# MARS3.net
KiCad netlist of a schematic drawn in Altium Designer
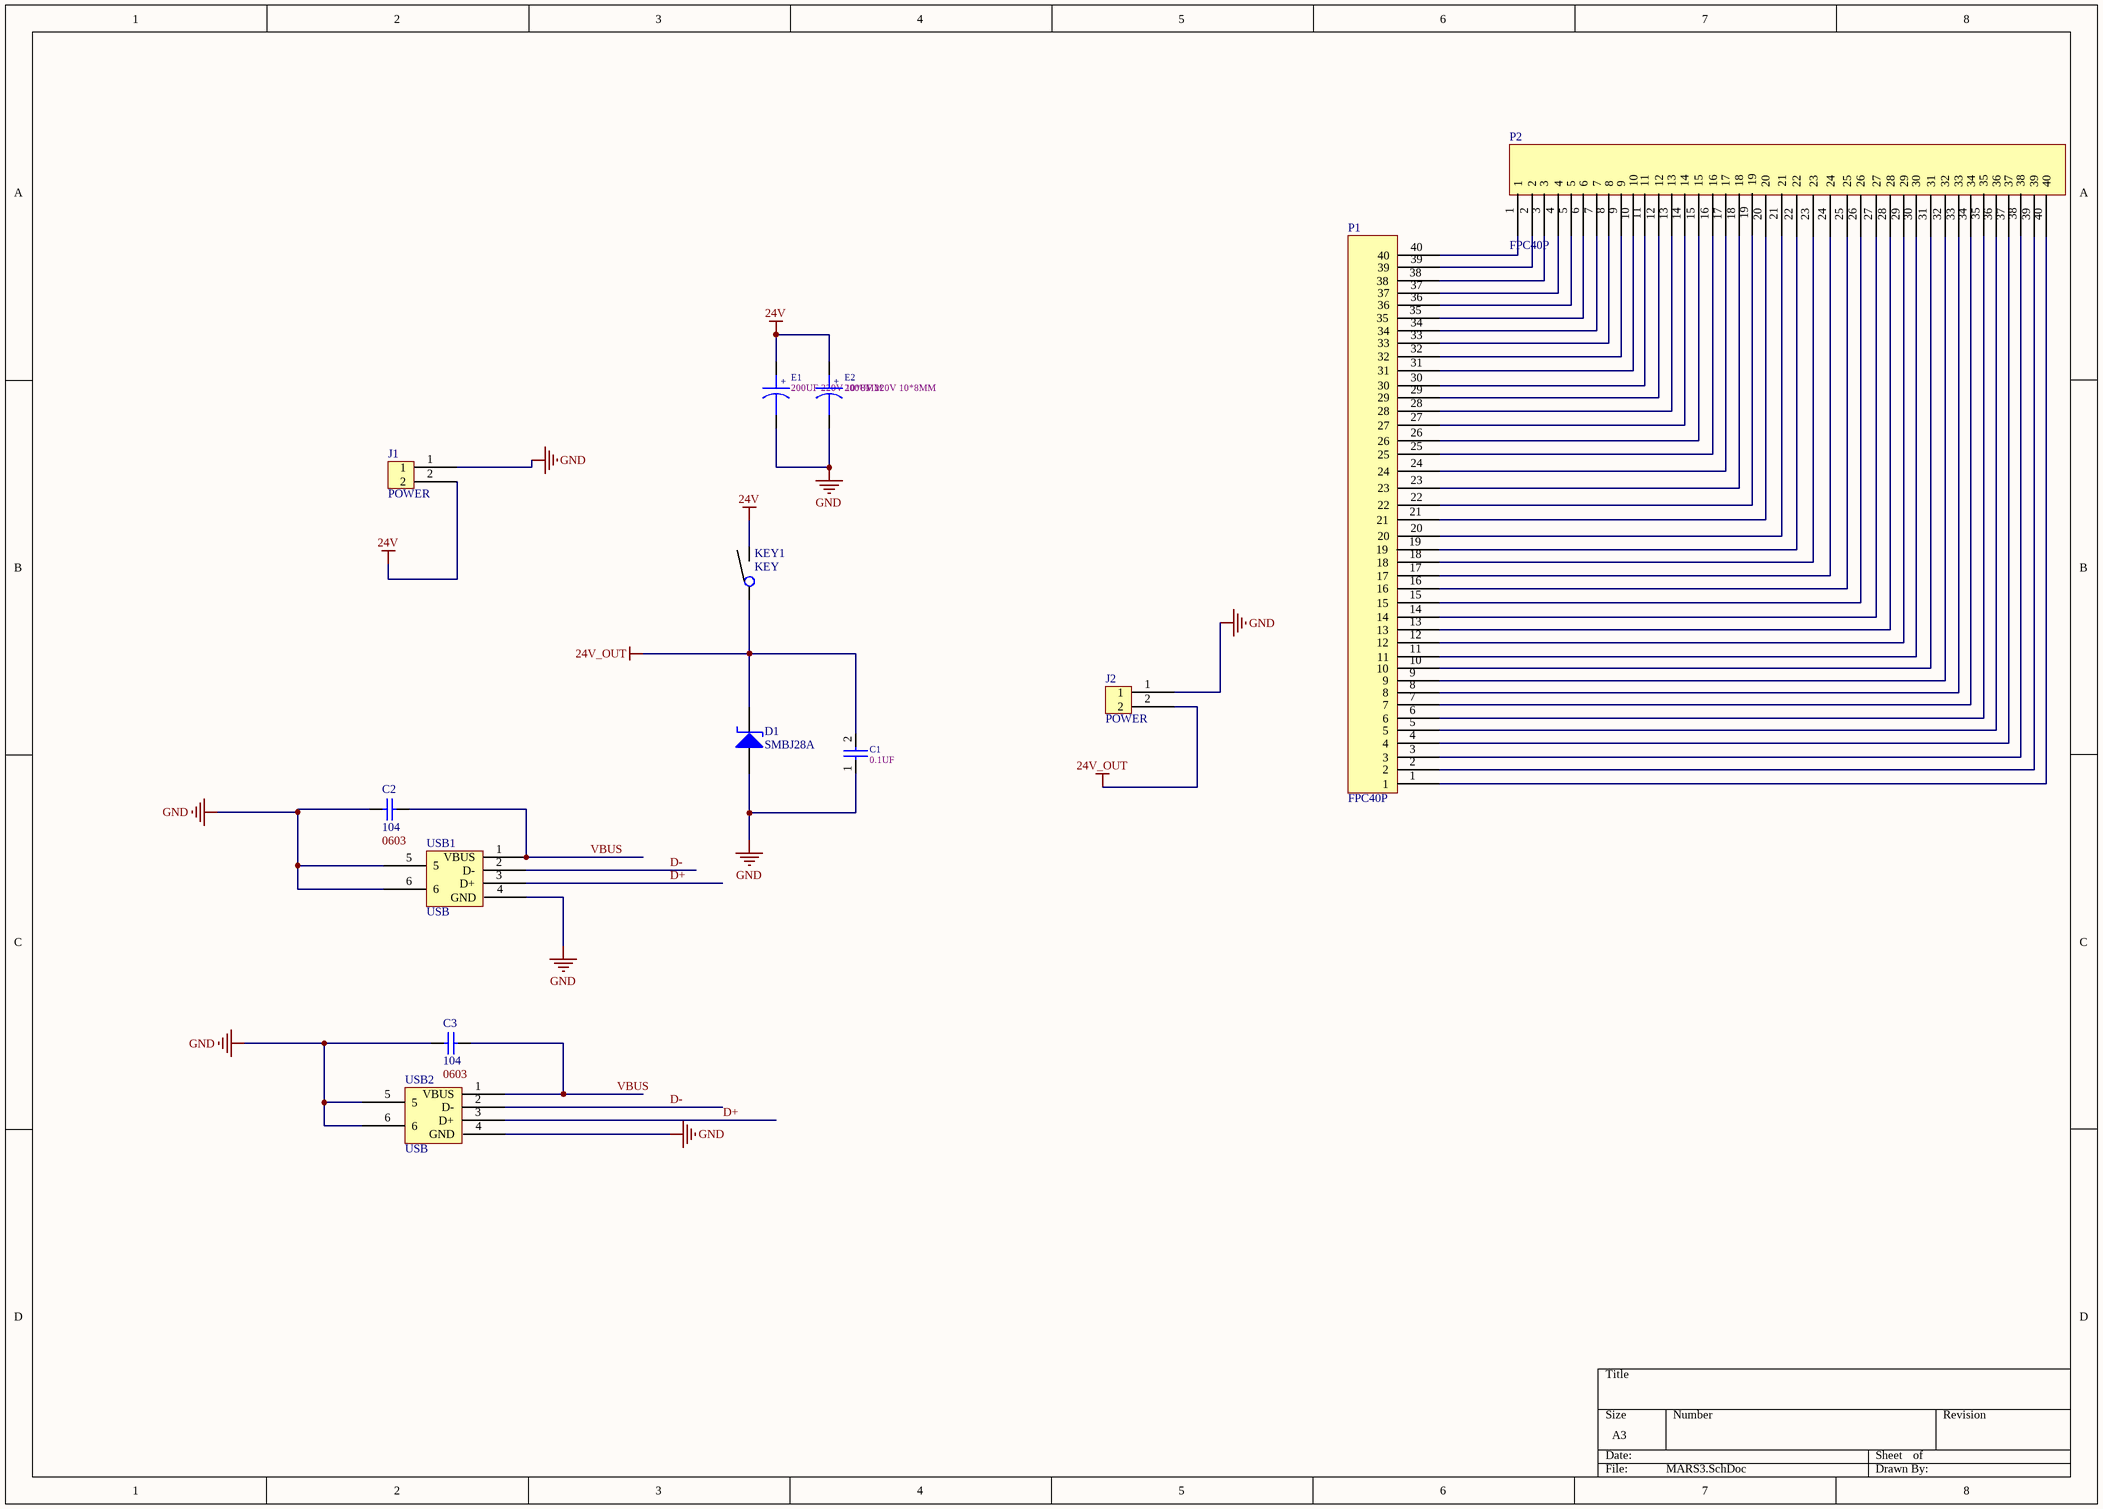
[diagram p0: MARS3.SchDoc]

(export (version "E")
  (design (tool "Eeschema 10.0.6"))
  (components
    (comp (ref "C1")
      (value "0.1UF")
      (footprint "C0603")
      (description "Capacitor")
      (libsource (lib "清洗固化") (part "CAP_10"))
    )
    (comp (ref "C2")
      (value "104")
      (footprint "0603")
      (description "Capacitor")
      (fields (field (name "PUBLISHER") "Altium Limited"))
      (libsource (lib "清洗机旋钮开关") (part "Cap_1"))
    )
    (comp (ref "C3")
      (value "104")
      (footprint "0603")
      (description "Capacitor")
      (fields (field (name "PUBLISHER") "Altium Limited"))
      (libsource (lib "清洗机旋钮开关") (part "Cap_1"))
    )
    (comp (ref "D1") (value "SMBJ28A") (footprint "DO214AA") (libsource (lib "清洗机旋钮开关") (part "TVS")))
    (comp (ref "E1")
      (value "200UF 220V 10*8MM")
      (footprint "CAPAE7766X80M")
      (description "Capacitor")
      (libsource (lib "清洗固化") (part "CAPACITOR POL"))
    )
    (comp (ref "E2")
      (value "200UF 220V 10*8MM")
      (footprint "CAPAE7766X80M")
      (description "Capacitor")
      (libsource (lib "清洗固化") (part "CAPACITOR POL"))
    )
    (comp (ref "J1")
      (value "POWER")
      (footprint "VH3.96_2P")
      (libsource (lib "VVH3.96_2P") (part "VH3.96_2P"))
    )
    (comp (ref "J2")
      (value "POWER")
      (footprint "VH3.96_2P")
      (libsource (lib "VVH3.96_2P") (part "VH3.96_2P"))
    )
    (comp (ref "KEY1") (value "KEY") (footprint "KEY") (libsource (lib "KEY") (part "KEY")))
    (comp (ref "P1") (value "FPC40P") (footprint "FPC0.5_40PIN") (libsource (lib "") (part "FPC40P_1")))
    (comp (ref "P2") (value "FPC40P") (footprint "FPC0.5_40PIN") (libsource (lib "FPC40P") (part "FPC40P")))
    (comp (ref "USB1") (value "USB") (footprint "USB_A_90_母座") (libsource (lib "USB_A母头") (part "USB_A母头")))
    (comp (ref "USB2") (value "USB") (footprint "USB10_SMT") (libsource (lib "USB_A母头") (part "USB_A母头")))
  )
  (nets
    (net (code "1") (name "/D+") (class "Default")
      (node (ref "USB1") (pin "3") (pinfunction "D+_3") (pintype "passive"))
      (node (ref "USB2") (pin "3") (pinfunction "D+_3") (pintype "passive"))
    )
    (net (code "2") (name "/D-") (class "Default")
      (node (ref "USB1") (pin "2") (pinfunction "D-_2") (pintype "passive"))
      (node (ref "USB2") (pin "2") (pinfunction "D-_2") (pintype "passive"))
    )
    (net (code "3") (name "/VBUS") (class "Default")
      (node (ref "C2") (pin "2") (pinfunction "2_2") (pintype "passive"))
      (node (ref "C3") (pin "2") (pinfunction "2_2") (pintype "passive"))
      (node (ref "USB1") (pin "1") (pinfunction "VBUS_1") (pintype "passive"))
      (node (ref "USB2") (pin "1") (pinfunction "VBUS_1") (pintype "passive"))
    )
    (net (code "4") (name "24V") (class "Default")
      (node (ref "E1") (pin "1") (pinfunction "1_1") (pintype "passive"))
      (node (ref "E2") (pin "1") (pinfunction "1_1") (pintype "passive"))
      (node (ref "J1") (pin "2") (pinfunction "2_2") (pintype "passive"))
      (node (ref "KEY1") (pin "2") (pinfunction "2_2") (pintype "passive"))
    )
    (net (code "5") (name "24V_OUT") (class "Default")
      (node (ref "C1") (pin "2") (pinfunction "2_2") (pintype "passive"))
      (node (ref "D1") (pin "2") (pinfunction "K_2") (pintype "passive"))
      (node (ref "J2") (pin "2") (pinfunction "2_2") (pintype "passive"))
      (node (ref "KEY1") (pin "1") (pinfunction "1_1") (pintype "passive"))
    )
    (net (code "6") (name "GND") (class "Default")
      (node (ref "C1") (pin "1") (pinfunction "1_1") (pintype "passive"))
      (node (ref "C2") (pin "1") (pinfunction "1_1") (pintype "passive"))
      (node (ref "C3") (pin "1") (pinfunction "1_1") (pintype "passive"))
      (node (ref "D1") (pin "1") (pinfunction "A_1") (pintype "passive"))
      (node (ref "E1") (pin "2") (pinfunction "2_2") (pintype "passive"))
      (node (ref "E2") (pin "2") (pinfunction "2_2") (pintype "passive"))
      (node (ref "J1") (pin "1") (pinfunction "1_1") (pintype "passive"))
      (node (ref "J2") (pin "1") (pinfunction "1_1") (pintype "passive"))
      (node (ref "USB1") (pin "4") (pinfunction "GND_4") (pintype "passive"))
      (node (ref "USB1") (pin "5") (pinfunction "5_5") (pintype "passive"))
      (node (ref "USB1") (pin "6") (pinfunction "6_6") (pintype "passive"))
      (node (ref "USB2") (pin "4") (pinfunction "GND_4") (pintype "passive"))
      (node (ref "USB2") (pin "5") (pinfunction "5_5") (pintype "passive"))
      (node (ref "USB2") (pin "6") (pinfunction "6_6") (pintype "passive"))
    )
    (net (code "7") (name "Net-(P1-Pad1)") (class "Default")
      (node (ref "P1") (pin "1") (pinfunction "1_1") (pintype "passive"))
      (node (ref "P2") (pin "40") (pinfunction "40_40") (pintype "passive"))
    )
    (net (code "8") (name "Net-(P1-Pad2)") (class "Default")
      (node (ref "P1") (pin "2") (pinfunction "2_2") (pintype "passive"))
      (node (ref "P2") (pin "39") (pinfunction "39_39") (pintype "passive"))
    )
    (net (code "9") (name "Net-(P1-Pad3)") (class "Default")
      (node (ref "P1") (pin "3") (pinfunction "3_3") (pintype "passive"))
      (node (ref "P2") (pin "38") (pinfunction "38_38") (pintype "passive"))
    )
    (net (code "10") (name "Net-(P1-Pad4)") (class "Default")
      (node (ref "P1") (pin "4") (pinfunction "4_4") (pintype "passive"))
      (node (ref "P2") (pin "37") (pinfunction "37_37") (pintype "passive"))
    )
    (net (code "11") (name "Net-(P1-Pad5)") (class "Default")
      (node (ref "P1") (pin "5") (pinfunction "5_5") (pintype "passive"))
      (node (ref "P2") (pin "36") (pinfunction "36_36") (pintype "passive"))
    )
    (net (code "12") (name "Net-(P1-Pad6)") (class "Default")
      (node (ref "P1") (pin "6") (pinfunction "6_6") (pintype "passive"))
      (node (ref "P2") (pin "35") (pinfunction "35_35") (pintype "passive"))
    )
    (net (code "13") (name "Net-(P1-Pad7)") (class "Default")
      (node (ref "P1") (pin "7") (pinfunction "7_7") (pintype "passive"))
      (node (ref "P2") (pin "34") (pinfunction "34_34") (pintype "passive"))
    )
    (net (code "14") (name "Net-(P1-Pad8)") (class "Default")
      (node (ref "P1") (pin "8") (pinfunction "8_8") (pintype "passive"))
      (node (ref "P2") (pin "33") (pinfunction "33_33") (pintype "passive"))
    )
    (net (code "15") (name "Net-(P1-Pad9)") (class "Default")
      (node (ref "P1") (pin "9") (pinfunction "9_9") (pintype "passive"))
      (node (ref "P2") (pin "32") (pinfunction "32_32") (pintype "passive"))
    )
    (net (code "16") (name "Net-(P1-Pad10)") (class "Default")
      (node (ref "P1") (pin "10") (pinfunction "10_10") (pintype "passive"))
      (node (ref "P2") (pin "31") (pinfunction "31_31") (pintype "passive"))
    )
    (net (code "17") (name "Net-(P1-Pad11)") (class "Default")
      (node (ref "P1") (pin "11") (pinfunction "11_11") (pintype "passive"))
      (node (ref "P2") (pin "30") (pinfunction "30_30") (pintype "passive"))
    )
    (net (code "18") (name "Net-(P1-Pad12)") (class "Default")
      (node (ref "P1") (pin "12") (pinfunction "12_12") (pintype "passive"))
      (node (ref "P2") (pin "29") (pinfunction "29_29") (pintype "passive"))
    )
    (net (code "19") (name "Net-(P1-Pad13)") (class "Default")
      (node (ref "P1") (pin "13") (pinfunction "13_13") (pintype "passive"))
      (node (ref "P2") (pin "28") (pinfunction "28_28") (pintype "passive"))
    )
    (net (code "20") (name "Net-(P1-Pad14)") (class "Default")
      (node (ref "P1") (pin "14") (pinfunction "14_14") (pintype "passive"))
      (node (ref "P2") (pin "27") (pinfunction "27_27") (pintype "passive"))
    )
    (net (code "21") (name "Net-(P1-Pad15)") (class "Default")
      (node (ref "P1") (pin "15") (pinfunction "15_15") (pintype "passive"))
      (node (ref "P2") (pin "26") (pinfunction "26_26") (pintype "passive"))
    )
    (net (code "22") (name "Net-(P1-Pad16)") (class "Default")
      (node (ref "P1") (pin "16") (pinfunction "16_16") (pintype "passive"))
      (node (ref "P2") (pin "25") (pinfunction "25_25") (pintype "passive"))
    )
    (net (code "23") (name "Net-(P1-Pad17)") (class "Default")
      (node (ref "P1") (pin "17") (pinfunction "17_17") (pintype "passive"))
      (node (ref "P2") (pin "24") (pinfunction "24_24") (pintype "passive"))
    )
    (net (code "24") (name "Net-(P1-Pad18)") (class "Default")
      (node (ref "P1") (pin "18") (pinfunction "18_18") (pintype "passive"))
      (node (ref "P2") (pin "23") (pinfunction "23_23") (pintype "passive"))
    )
    (net (code "25") (name "Net-(P1-Pad19)") (class "Default")
      (node (ref "P1") (pin "19") (pinfunction "19_19") (pintype "passive"))
      (node (ref "P2") (pin "22") (pinfunction "22_22") (pintype "passive"))
    )
    (net (code "26") (name "Net-(P1-Pad20)") (class "Default")
      (node (ref "P1") (pin "20") (pinfunction "20_20") (pintype "passive"))
      (node (ref "P2") (pin "21") (pinfunction "21_21") (pintype "passive"))
    )
    (net (code "27") (name "Net-(P1-Pad21)") (class "Default")
      (node (ref "P1") (pin "21") (pinfunction "21_21") (pintype "passive"))
      (node (ref "P2") (pin "20") (pinfunction "20_20") (pintype "passive"))
    )
    (net (code "28") (name "Net-(P1-Pad22)") (class "Default")
      (node (ref "P1") (pin "22") (pinfunction "22_22") (pintype "passive"))
      (node (ref "P2") (pin "19") (pinfunction "19_19") (pintype "passive"))
    )
    (net (code "29") (name "Net-(P1-Pad23)") (class "Default")
      (node (ref "P1") (pin "23") (pinfunction "23_23") (pintype "passive"))
      (node (ref "P2") (pin "18") (pinfunction "18_18") (pintype "passive"))
    )
    (net (code "30") (name "Net-(P1-Pad24)") (class "Default")
      (node (ref "P1") (pin "24") (pinfunction "24_24") (pintype "passive"))
      (node (ref "P2") (pin "17") (pinfunction "17_17") (pintype "passive"))
    )
    (net (code "31") (name "Net-(P1-Pad25)") (class "Default")
      (node (ref "P1") (pin "25") (pinfunction "25_25") (pintype "passive"))
      (node (ref "P2") (pin "16") (pinfunction "16_16") (pintype "passive"))
    )
    (net (code "32") (name "Net-(P1-Pad26)") (class "Default")
      (node (ref "P1") (pin "26") (pinfunction "26_26") (pintype "passive"))
      (node (ref "P2") (pin "15") (pinfunction "15_15") (pintype "passive"))
    )
    (net (code "33") (name "Net-(P1-Pad27)") (class "Default")
      (node (ref "P1") (pin "27") (pinfunction "27_27") (pintype "passive"))
      (node (ref "P2") (pin "14") (pinfunction "14_14") (pintype "passive"))
    )
    (net (code "34") (name "Net-(P1-Pad28)") (class "Default")
      (node (ref "P1") (pin "28") (pinfunction "28_28") (pintype "passive"))
      (node (ref "P2") (pin "13") (pinfunction "13_13") (pintype "passive"))
    )
    (net (code "35") (name "Net-(P1-Pad29)") (class "Default")
      (node (ref "P1") (pin "29") (pinfunction "29_29") (pintype "passive"))
      (node (ref "P2") (pin "12") (pinfunction "12_12") (pintype "passive"))
    )
    (net (code "36") (name "Net-(P1-Pad30)") (class "Default")
      (node (ref "P1") (pin "30") (pinfunction "30_30") (pintype "passive"))
      (node (ref "P2") (pin "11") (pinfunction "11_11") (pintype "passive"))
    )
    (net (code "37") (name "Net-(P1-Pad31)") (class "Default")
      (node (ref "P1") (pin "31") (pinfunction "31_31") (pintype "passive"))
      (node (ref "P2") (pin "10") (pinfunction "10_10") (pintype "passive"))
    )
    (net (code "38") (name "Net-(P1-Pad32)") (class "Default")
      (node (ref "P1") (pin "32") (pinfunction "32_32") (pintype "passive"))
      (node (ref "P2") (pin "9") (pinfunction "9_9") (pintype "passive"))
    )
    (net (code "39") (name "Net-(P1-Pad33)") (class "Default")
      (node (ref "P1") (pin "33") (pinfunction "33_33") (pintype "passive"))
      (node (ref "P2") (pin "8") (pinfunction "8_8") (pintype "passive"))
    )
    (net (code "40") (name "Net-(P1-Pad34)") (class "Default")
      (node (ref "P1") (pin "34") (pinfunction "34_34") (pintype "passive"))
      (node (ref "P2") (pin "7") (pinfunction "7_7") (pintype "passive"))
    )
    (net (code "41") (name "Net-(P1-Pad35)") (class "Default")
      (node (ref "P1") (pin "35") (pinfunction "35_35") (pintype "passive"))
      (node (ref "P2") (pin "6") (pinfunction "6_6") (pintype "passive"))
    )
    (net (code "42") (name "Net-(P1-Pad36)") (class "Default")
      (node (ref "P1") (pin "36") (pinfunction "36_36") (pintype "passive"))
      (node (ref "P2") (pin "5") (pinfunction "5_5") (pintype "passive"))
    )
    (net (code "43") (name "Net-(P1-Pad37)") (class "Default")
      (node (ref "P1") (pin "37") (pinfunction "37_37") (pintype "passive"))
      (node (ref "P2") (pin "4") (pinfunction "4_4") (pintype "passive"))
    )
    (net (code "44") (name "Net-(P1-Pad38)") (class "Default")
      (node (ref "P1") (pin "38") (pinfunction "38_38") (pintype "passive"))
      (node (ref "P2") (pin "3") (pinfunction "3_3") (pintype "passive"))
    )
    (net (code "45") (name "Net-(P1-Pad39)") (class "Default")
      (node (ref "P1") (pin "39") (pinfunction "39_39") (pintype "passive"))
      (node (ref "P2") (pin "2") (pinfunction "2_2") (pintype "passive"))
    )
    (net (code "46") (name "Net-(P1-Pad40)") (class "Default")
      (node (ref "P1") (pin "40") (pinfunction "40_40") (pintype "passive"))
      (node (ref "P2") (pin "1") (pinfunction "1_1") (pintype "passive"))
    )
  )
)
